# DAC.net
KiCad netlist of a schematic drawn in Altium Designer
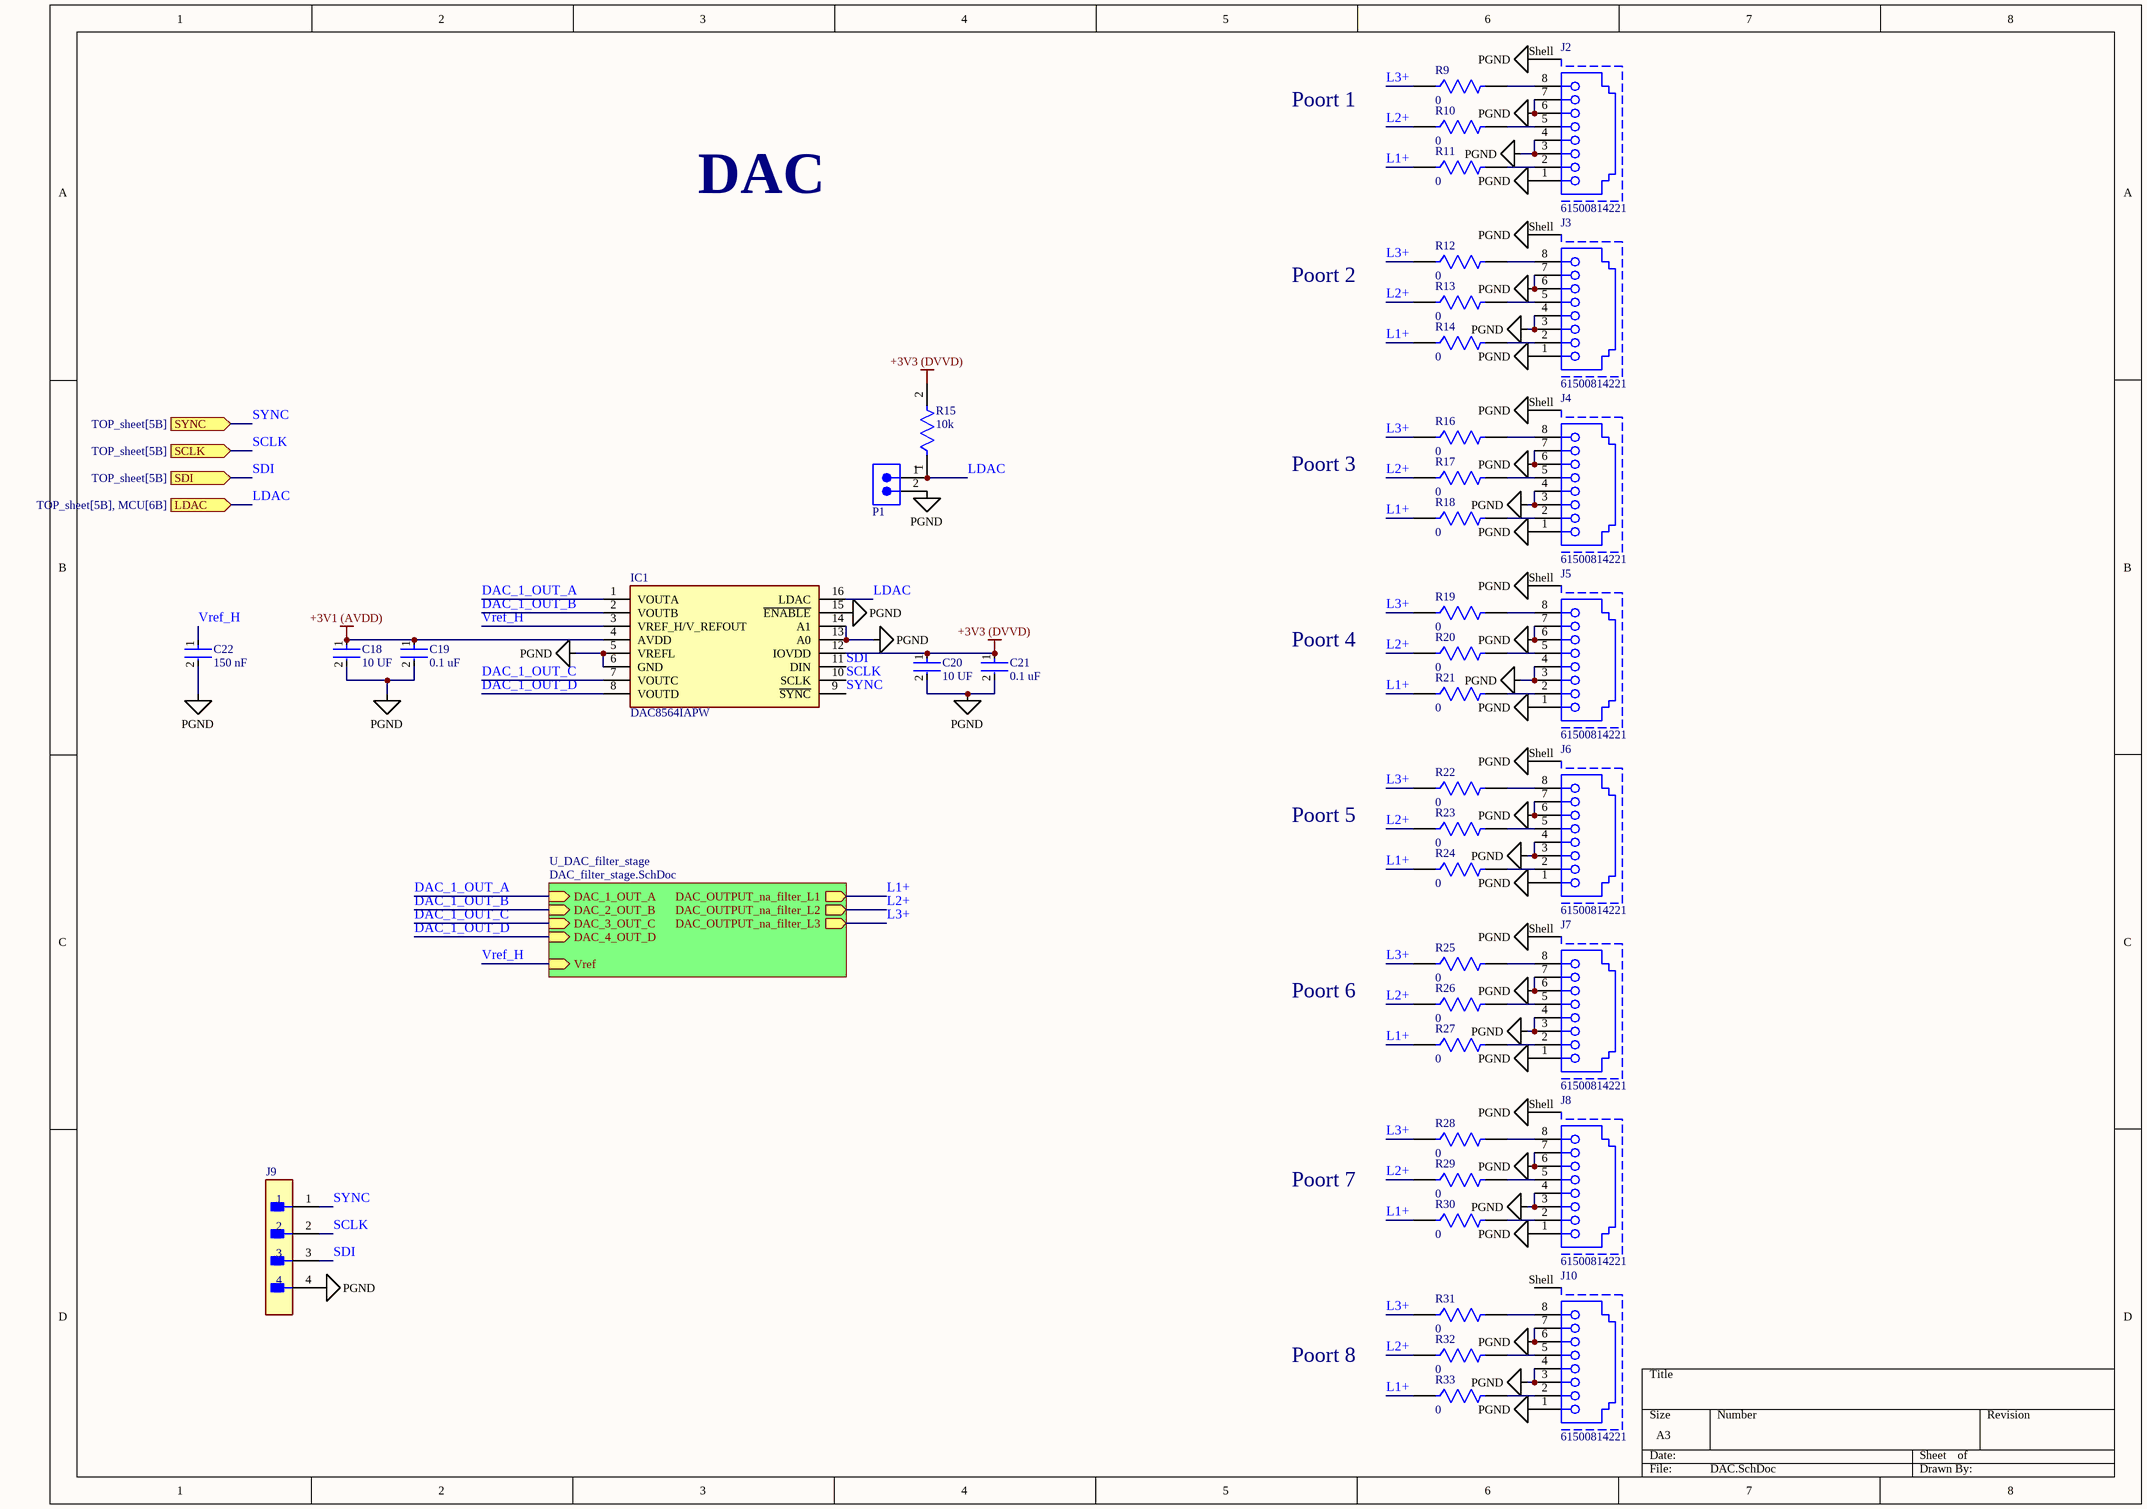
[diagram p0: DAC.SchDoc]

(export (version "E")
  (design (tool "Eeschema 10.0.6"))
  (components
    (comp (ref "C18")
      (value "10 UF")
      (footprint "FP-CC0603-DA-MFG")
      (description "CAP CER 10 UF 16V X7R 0603")
      (fields
        (field (name "OCTOPART") "https://octopart.com/cc0603krx7r7bb104-yageo-192941")
        (field (name "TOLERANCE") "0.1")
      )
      (libsource (lib "Altium Content Vault") (part "11868f565c42a9108669ba33697ecf6"))
    )
    (comp (ref "C19")
      (value "0.1 uF")
      (footprint "FP-CC0603-DA-MFG")
      (description "CAP CER 0.1UF 16V X7R 0603")
      (fields
        (field (name "OCTOPART") "https://octopart.com/cc0603krx7r7bb104-yageo-192941")
        (field (name "TOLERANCE") "0.1")
      )
      (libsource (lib "Altium Content Vault") (part "11868f565c42a9108669ba33697ecf6"))
    )
    (comp (ref "C20")
      (value "10 UF")
      (footprint "FP-CC0603-DA-MFG")
      (description "CAP CER 10 UF 16V X7R 0603")
      (fields
        (field (name "OCTOPART") "https://octopart.com/cc0603krx7r7bb104-yageo-192941")
        (field (name "TOLERANCE") "0.1")
      )
      (libsource (lib "Altium Content Vault") (part "11868f565c42a9108669ba33697ecf6"))
    )
    (comp (ref "C21")
      (value "0.1 uF")
      (footprint "FP-CC0603-DA-MFG")
      (description "CAP CER 0.1UF 16V X7R 0603")
      (fields
        (field (name "OCTOPART") "https://octopart.com/cc0603krx7r7bb104-yageo-192941")
        (field (name "TOLERANCE") "0.1")
      )
      (libsource (lib "Altium Content Vault") (part "11868f565c42a9108669ba33697ecf6"))
    )
    (comp (ref "C22")
      (value "150 nF")
      (footprint "FP-CC0603-DA-MFG")
      (description "CAP CER 0.1UF 16V X7R 0603")
      (fields
        (field (name "OCTOPART") "https://octopart.com/cc0603krx7r7bb104-yageo-192941")
        (field (name "TOLERANCE") "0.1")
      )
      (libsource (lib "Altium Content Vault") (part "11868f565c42a9108669ba33697ecf6"))
    )
    (comp (ref "IC1")
      (value "DAC8564IAPW")
      (footprint "SamacSys:SOP65P640X120-16N")
      (description "Integrated Circuit")
      (fields (field (name "MOUSER PART NUMBER") "595-DAC8564IAPW"))
      (libsource (lib "*") (part "DAC8564IAPW"))
    )
    (comp (ref "J2")
      (value "61500814221")
      (footprint "61500814221")
      (libsource (lib "Altium Content Vault") (part "8P8C - 1 Port - Shielded"))
    )
    (comp (ref "J3")
      (value "61500814221")
      (footprint "61500814221")
      (libsource (lib "Altium Content Vault") (part "8P8C - 1 Port - Shielded"))
    )
    (comp (ref "J4")
      (value "61500814221")
      (footprint "61500814221")
      (libsource (lib "Altium Content Vault") (part "8P8C - 1 Port - Shielded"))
    )
    (comp (ref "J5")
      (value "61500814221")
      (footprint "61500814221")
      (libsource (lib "Altium Content Vault") (part "8P8C - 1 Port - Shielded"))
    )
    (comp (ref "J6")
      (value "61500814221")
      (footprint "61500814221")
      (libsource (lib "Altium Content Vault") (part "8P8C - 1 Port - Shielded"))
    )
    (comp (ref "J7")
      (value "61500814221")
      (footprint "61500814221")
      (libsource (lib "Altium Content Vault") (part "8P8C - 1 Port - Shielded"))
    )
    (comp (ref "J8")
      (value "61500814221")
      (footprint "61500814221")
      (libsource (lib "Altium Content Vault") (part "8P8C - 1 Port - Shielded"))
    )
    (comp (ref "J9")
      (value "TSW-104-22-G-S")
      (footprint "FP-TSW-104-22-G-S-MFG")
      (description "GENERIC PART NUMBER: GPHA-1X04\r\nCONN HEADER VERT 4POS 2.54MM")
      (fields (field (name "GENERIC PART NUMBER") "GPHA-1X04"))
      (libsource (lib "Altium Content Vault") (part "299a8cea1bdcbc3624fe62c390fa72c"))
    )
    (comp (ref "J10")
      (value "61500814221")
      (footprint "61500814221")
      (libsource (lib "Altium Content Vault") (part "8P8C - 1 Port - Shielded"))
    )
    (comp (ref "P1")
      (value "TSW-102-26-T-S")
      (footprint "SMTC-TSW-102-26-XX-S")
      (description "0.025\" SQ Post Header, Through-hole, Vertical, -55 to 105 degC, 2.54 mm Pitch, 2-Pin, Male, RoHS")
      (fields (field (name "MANUFACTURER") "Samtec"))
      (libsource (lib "Altium Content Vault") (part "SMTC-TSW-102-X-X-S-X"))
    )
    (comp (ref "R9")
      (value "0")
      (footprint "FP-CRCW1206-MFG")
      (description "CRCW12060000ZSTA Zero Ohm Resistor, Jumper, 1206 [3216 Metric], Thick Film, 250 mW, Surface Mount")
      (libsource (lib "Altium Content Vault") (part "1029c3af85768c4190bb7ad29bc67b5"))
    )
    (comp (ref "R10")
      (value "0")
      (footprint "FP-CRCW1206-MFG")
      (description "CRCW12060000ZSTA Zero Ohm Resistor, Jumper, 1206 [3216 Metric], Thick Film, 250 mW, Surface Mount")
      (libsource (lib "Altium Content Vault") (part "1029c3af85768c4190bb7ad29bc67b5"))
    )
    (comp (ref "R11")
      (value "0")
      (footprint "FP-CRCW1206-MFG")
      (description "CRCW12060000ZSTA Zero Ohm Resistor, Jumper, 1206 [3216 Metric], Thick Film, 250 mW, Surface Mount")
      (libsource (lib "Altium Content Vault") (part "1029c3af85768c4190bb7ad29bc67b5"))
    )
    (comp (ref "R12")
      (value "0")
      (footprint "FP-CRCW1206-MFG")
      (description "CRCW12060000ZSTA Zero Ohm Resistor, Jumper, 1206 [3216 Metric], Thick Film, 250 mW, Surface Mount")
      (libsource (lib "Altium Content Vault") (part "1029c3af85768c4190bb7ad29bc67b5"))
    )
    (comp (ref "R13")
      (value "0")
      (footprint "FP-CRCW1206-MFG")
      (description "CRCW12060000ZSTA Zero Ohm Resistor, Jumper, 1206 [3216 Metric], Thick Film, 250 mW, Surface Mount")
      (libsource (lib "Altium Content Vault") (part "1029c3af85768c4190bb7ad29bc67b5"))
    )
    (comp (ref "R14")
      (value "0")
      (footprint "FP-CRCW1206-MFG")
      (description "CRCW12060000ZSTA Zero Ohm Resistor, Jumper, 1206 [3216 Metric], Thick Film, 250 mW, Surface Mount")
      (libsource (lib "Altium Content Vault") (part "1029c3af85768c4190bb7ad29bc67b5"))
    )
    (comp (ref "R15")
      (value "10k")
      (footprint "FP-RC1608-IPC_B")
      (description "Res Thick Film 0603 11kΩ 1% 0.1W ±100ppm/°C Molded SMD T/R")
      (fields (field (name "TOLERANCE") "1%"))
      (libsource (lib "") (part "1029c3af85768c4190bb7ad29bc67b5_1"))
    )
    (comp (ref "R16")
      (value "0")
      (footprint "FP-CRCW1206-MFG")
      (description "CRCW12060000ZSTA Zero Ohm Resistor, Jumper, 1206 [3216 Metric], Thick Film, 250 mW, Surface Mount")
      (libsource (lib "Altium Content Vault") (part "1029c3af85768c4190bb7ad29bc67b5"))
    )
    (comp (ref "R17")
      (value "0")
      (footprint "FP-CRCW1206-MFG")
      (description "CRCW12060000ZSTA Zero Ohm Resistor, Jumper, 1206 [3216 Metric], Thick Film, 250 mW, Surface Mount")
      (libsource (lib "Altium Content Vault") (part "1029c3af85768c4190bb7ad29bc67b5"))
    )
    (comp (ref "R18")
      (value "0")
      (footprint "FP-CRCW1206-MFG")
      (description "CRCW12060000ZSTA Zero Ohm Resistor, Jumper, 1206 [3216 Metric], Thick Film, 250 mW, Surface Mount")
      (libsource (lib "Altium Content Vault") (part "1029c3af85768c4190bb7ad29bc67b5"))
    )
    (comp (ref "R19")
      (value "0")
      (footprint "FP-CRCW1206-MFG")
      (description "CRCW12060000ZSTA Zero Ohm Resistor, Jumper, 1206 [3216 Metric], Thick Film, 250 mW, Surface Mount")
      (libsource (lib "Altium Content Vault") (part "1029c3af85768c4190bb7ad29bc67b5"))
    )
    (comp (ref "R20")
      (value "0")
      (footprint "FP-CRCW1206-MFG")
      (description "CRCW12060000ZSTA Zero Ohm Resistor, Jumper, 1206 [3216 Metric], Thick Film, 250 mW, Surface Mount")
      (libsource (lib "Altium Content Vault") (part "1029c3af85768c4190bb7ad29bc67b5"))
    )
    (comp (ref "R21")
      (value "0")
      (footprint "FP-CRCW1206-MFG")
      (description "CRCW12060000ZSTA Zero Ohm Resistor, Jumper, 1206 [3216 Metric], Thick Film, 250 mW, Surface Mount")
      (libsource (lib "Altium Content Vault") (part "1029c3af85768c4190bb7ad29bc67b5"))
    )
    (comp (ref "R22")
      (value "0")
      (footprint "FP-CRCW1206-MFG")
      (description "CRCW12060000ZSTA Zero Ohm Resistor, Jumper, 1206 [3216 Metric], Thick Film, 250 mW, Surface Mount")
      (libsource (lib "Altium Content Vault") (part "1029c3af85768c4190bb7ad29bc67b5"))
    )
    (comp (ref "R23")
      (value "0")
      (footprint "FP-CRCW1206-MFG")
      (description "CRCW12060000ZSTA Zero Ohm Resistor, Jumper, 1206 [3216 Metric], Thick Film, 250 mW, Surface Mount")
      (libsource (lib "Altium Content Vault") (part "1029c3af85768c4190bb7ad29bc67b5"))
    )
    (comp (ref "R24")
      (value "0")
      (footprint "FP-CRCW1206-MFG")
      (description "CRCW12060000ZSTA Zero Ohm Resistor, Jumper, 1206 [3216 Metric], Thick Film, 250 mW, Surface Mount")
      (libsource (lib "Altium Content Vault") (part "1029c3af85768c4190bb7ad29bc67b5"))
    )
    (comp (ref "R25")
      (value "0")
      (footprint "FP-CRCW1206-MFG")
      (description "CRCW12060000ZSTA Zero Ohm Resistor, Jumper, 1206 [3216 Metric], Thick Film, 250 mW, Surface Mount")
      (libsource (lib "Altium Content Vault") (part "1029c3af85768c4190bb7ad29bc67b5"))
    )
    (comp (ref "R26")
      (value "0")
      (footprint "FP-CRCW1206-MFG")
      (description "CRCW12060000ZSTA Zero Ohm Resistor, Jumper, 1206 [3216 Metric], Thick Film, 250 mW, Surface Mount")
      (libsource (lib "Altium Content Vault") (part "1029c3af85768c4190bb7ad29bc67b5"))
    )
    (comp (ref "R27")
      (value "0")
      (footprint "FP-CRCW1206-MFG")
      (description "CRCW12060000ZSTA Zero Ohm Resistor, Jumper, 1206 [3216 Metric], Thick Film, 250 mW, Surface Mount")
      (libsource (lib "Altium Content Vault") (part "1029c3af85768c4190bb7ad29bc67b5"))
    )
    (comp (ref "R28")
      (value "0")
      (footprint "FP-CRCW1206-MFG")
      (description "CRCW12060000ZSTA Zero Ohm Resistor, Jumper, 1206 [3216 Metric], Thick Film, 250 mW, Surface Mount")
      (libsource (lib "Altium Content Vault") (part "1029c3af85768c4190bb7ad29bc67b5"))
    )
    (comp (ref "R29")
      (value "0")
      (footprint "FP-CRCW1206-MFG")
      (description "CRCW12060000ZSTA Zero Ohm Resistor, Jumper, 1206 [3216 Metric], Thick Film, 250 mW, Surface Mount")
      (libsource (lib "Altium Content Vault") (part "1029c3af85768c4190bb7ad29bc67b5"))
    )
    (comp (ref "R30")
      (value "0")
      (footprint "FP-CRCW1206-MFG")
      (description "CRCW12060000ZSTA Zero Ohm Resistor, Jumper, 1206 [3216 Metric], Thick Film, 250 mW, Surface Mount")
      (libsource (lib "Altium Content Vault") (part "1029c3af85768c4190bb7ad29bc67b5"))
    )
    (comp (ref "R31")
      (value "0")
      (footprint "FP-CRCW1206-MFG")
      (description "CRCW12060000ZSTA Zero Ohm Resistor, Jumper, 1206 [3216 Metric], Thick Film, 250 mW, Surface Mount")
      (libsource (lib "Altium Content Vault") (part "1029c3af85768c4190bb7ad29bc67b5"))
    )
    (comp (ref "R32")
      (value "0")
      (footprint "FP-CRCW1206-MFG")
      (description "CRCW12060000ZSTA Zero Ohm Resistor, Jumper, 1206 [3216 Metric], Thick Film, 250 mW, Surface Mount")
      (libsource (lib "Altium Content Vault") (part "1029c3af85768c4190bb7ad29bc67b5"))
    )
    (comp (ref "R33")
      (value "0")
      (footprint "FP-CRCW1206-MFG")
      (description "CRCW12060000ZSTA Zero Ohm Resistor, Jumper, 1206 [3216 Metric], Thick Film, 250 mW, Surface Mount")
      (libsource (lib "Altium Content Vault") (part "1029c3af85768c4190bb7ad29bc67b5"))
    )
  )
  (nets
    (net (code "1") (name "+3V1 (AVDD)") (class "Default")
      (node (ref "C18") (pin "1") (pinfunction "1_1") (pintype "passive"))
      (node (ref "C19") (pin "1") (pinfunction "1_1") (pintype "passive"))
      (node (ref "IC1") (pin "4") (pinfunction "AVDD_4") (pintype "passive"))
    )
    (net (code "2") (name "+3V3 (DVVD)") (class "Default")
      (node (ref "C20") (pin "1") (pinfunction "1_1") (pintype "passive"))
      (node (ref "C21") (pin "1") (pinfunction "1_1") (pintype "passive"))
      (node (ref "IC1") (pin "12") (pinfunction "IOVDD_12") (pintype "passive"))
      (node (ref "R15") (pin "2") (pinfunction "2_2") (pintype "passive"))
    )
    (net (code "3") (name "/DAC_1_OUT_A") (class "Default")
      (node (ref "IC1") (pin "1") (pinfunction "VOUTA_1") (pintype "passive"))
    )
    (net (code "4") (name "/DAC_1_OUT_B") (class "Default")
      (node (ref "IC1") (pin "2") (pinfunction "VOUTB_2") (pintype "passive"))
    )
    (net (code "5") (name "/DAC_1_OUT_C") (class "Default")
      (node (ref "IC1") (pin "7") (pinfunction "VOUTC_7") (pintype "passive"))
    )
    (net (code "6") (name "/DAC_1_OUT_D") (class "Default")
      (node (ref "IC1") (pin "8") (pinfunction "VOUTD_8") (pintype "passive"))
    )
    (net (code "7") (name "/L1+") (class "Default")
      (node (ref "R11") (pin "1") (pinfunction "1_1") (pintype "passive"))
      (node (ref "R14") (pin "1") (pinfunction "1_1") (pintype "passive"))
      (node (ref "R18") (pin "1") (pinfunction "1_1") (pintype "passive"))
      (node (ref "R21") (pin "1") (pinfunction "1_1") (pintype "passive"))
      (node (ref "R24") (pin "1") (pinfunction "1_1") (pintype "passive"))
      (node (ref "R27") (pin "1") (pinfunction "1_1") (pintype "passive"))
      (node (ref "R30") (pin "1") (pinfunction "1_1") (pintype "passive"))
      (node (ref "R33") (pin "1") (pinfunction "1_1") (pintype "passive"))
    )
    (net (code "8") (name "/L2+") (class "Default")
      (node (ref "R10") (pin "1") (pinfunction "1_1") (pintype "passive"))
      (node (ref "R13") (pin "1") (pinfunction "1_1") (pintype "passive"))
      (node (ref "R17") (pin "1") (pinfunction "1_1") (pintype "passive"))
      (node (ref "R20") (pin "1") (pinfunction "1_1") (pintype "passive"))
      (node (ref "R23") (pin "1") (pinfunction "1_1") (pintype "passive"))
      (node (ref "R26") (pin "1") (pinfunction "1_1") (pintype "passive"))
      (node (ref "R29") (pin "1") (pinfunction "1_1") (pintype "passive"))
      (node (ref "R32") (pin "1") (pinfunction "1_1") (pintype "passive"))
    )
    (net (code "9") (name "/L3+") (class "Default")
      (node (ref "R12") (pin "1") (pinfunction "1_1") (pintype "passive"))
      (node (ref "R16") (pin "1") (pinfunction "1_1") (pintype "passive"))
      (node (ref "R19") (pin "1") (pinfunction "1_1") (pintype "passive"))
      (node (ref "R22") (pin "1") (pinfunction "1_1") (pintype "passive"))
      (node (ref "R25") (pin "1") (pinfunction "1_1") (pintype "passive"))
      (node (ref "R28") (pin "1") (pinfunction "1_1") (pintype "passive"))
      (node (ref "R31") (pin "1") (pinfunction "1_1") (pintype "passive"))
      (node (ref "R9") (pin "1") (pinfunction "1_1") (pintype "passive"))
    )
    (net (code "10") (name "/LDAC") (class "Default")
      (node (ref "IC1") (pin "16") (pinfunction "LDAC_16") (pintype "passive"))
      (node (ref "P1") (pin "1") (pinfunction "1_1") (pintype "passive"))
      (node (ref "R15") (pin "1") (pinfunction "1_1") (pintype "passive"))
    )
    (net (code "11") (name "/SCLK") (class "Default")
      (node (ref "IC1") (pin "10") (pinfunction "SCLK_10") (pintype "passive"))
      (node (ref "J9") (pin "2") (pinfunction "2_2") (pintype "passive"))
    )
    (net (code "12") (name "/SDI") (class "Default")
      (node (ref "IC1") (pin "11") (pinfunction "DIN_11") (pintype "passive"))
      (node (ref "J9") (pin "3") (pinfunction "3_3") (pintype "passive"))
    )
    (net (code "13") (name "/SYNC") (class "Default")
      (node (ref "IC1") (pin "9") (pinfunction "~{SYNC}_9") (pintype "passive"))
      (node (ref "J9") (pin "1") (pinfunction "1_1") (pintype "passive"))
    )
    (net (code "14") (name "/Vref_H") (class "Default")
      (node (ref "C22") (pin "1") (pinfunction "1_1") (pintype "passive"))
      (node (ref "IC1") (pin "3") (pinfunction "VREF_H/V_REFOUT_3") (pintype "passive"))
    )
    (net (code "15") (name "Net-(J2-Pad2)") (class "Default")
      (node (ref "J2") (pin "2") (pinfunction "2_2") (pintype "passive"))
      (node (ref "R11") (pin "2") (pinfunction "2_2") (pintype "passive"))
    )
    (net (code "16") (name "Net-(J2-Pad5)") (class "Default")
      (node (ref "J2") (pin "5") (pinfunction "5_5") (pintype "passive"))
      (node (ref "R10") (pin "2") (pinfunction "2_2") (pintype "passive"))
    )
    (net (code "17") (name "Net-(J2-Pad8)") (class "Default")
      (node (ref "J2") (pin "8") (pinfunction "8_8") (pintype "passive"))
      (node (ref "R9") (pin "2") (pinfunction "2_2") (pintype "passive"))
    )
    (net (code "18") (name "Net-(J3-Pad2)") (class "Default")
      (node (ref "J3") (pin "2") (pinfunction "2_2") (pintype "passive"))
      (node (ref "R14") (pin "2") (pinfunction "2_2") (pintype "passive"))
    )
    (net (code "19") (name "Net-(J3-Pad5)") (class "Default")
      (node (ref "J3") (pin "5") (pinfunction "5_5") (pintype "passive"))
      (node (ref "R13") (pin "2") (pinfunction "2_2") (pintype "passive"))
    )
    (net (code "20") (name "Net-(J3-Pad8)") (class "Default")
      (node (ref "J3") (pin "8") (pinfunction "8_8") (pintype "passive"))
      (node (ref "R12") (pin "2") (pinfunction "2_2") (pintype "passive"))
    )
    (net (code "21") (name "Net-(J4-Pad2)") (class "Default")
      (node (ref "J4") (pin "2") (pinfunction "2_2") (pintype "passive"))
      (node (ref "R18") (pin "2") (pinfunction "2_2") (pintype "passive"))
    )
    (net (code "22") (name "Net-(J4-Pad5)") (class "Default")
      (node (ref "J4") (pin "5") (pinfunction "5_5") (pintype "passive"))
      (node (ref "R17") (pin "2") (pinfunction "2_2") (pintype "passive"))
    )
    (net (code "23") (name "Net-(J4-Pad8)") (class "Default")
      (node (ref "J4") (pin "8") (pinfunction "8_8") (pintype "passive"))
      (node (ref "R16") (pin "2") (pinfunction "2_2") (pintype "passive"))
    )
    (net (code "24") (name "Net-(J5-Pad2)") (class "Default")
      (node (ref "J5") (pin "2") (pinfunction "2_2") (pintype "passive"))
      (node (ref "R21") (pin "2") (pinfunction "2_2") (pintype "passive"))
    )
    (net (code "25") (name "Net-(J5-Pad5)") (class "Default")
      (node (ref "J5") (pin "5") (pinfunction "5_5") (pintype "passive"))
      (node (ref "R20") (pin "2") (pinfunction "2_2") (pintype "passive"))
    )
    (net (code "26") (name "Net-(J5-Pad8)") (class "Default")
      (node (ref "J5") (pin "8") (pinfunction "8_8") (pintype "passive"))
      (node (ref "R19") (pin "2") (pinfunction "2_2") (pintype "passive"))
    )
    (net (code "27") (name "Net-(J6-Pad2)") (class "Default")
      (node (ref "J6") (pin "2") (pinfunction "2_2") (pintype "passive"))
      (node (ref "R24") (pin "2") (pinfunction "2_2") (pintype "passive"))
    )
    (net (code "28") (name "Net-(J6-Pad5)") (class "Default")
      (node (ref "J6") (pin "5") (pinfunction "5_5") (pintype "passive"))
      (node (ref "R23") (pin "2") (pinfunction "2_2") (pintype "passive"))
    )
    (net (code "29") (name "Net-(J6-Pad8)") (class "Default")
      (node (ref "J6") (pin "8") (pinfunction "8_8") (pintype "passive"))
      (node (ref "R22") (pin "2") (pinfunction "2_2") (pintype "passive"))
    )
    (net (code "30") (name "Net-(J7-Pad2)") (class "Default")
      (node (ref "J7") (pin "2") (pinfunction "2_2") (pintype "passive"))
      (node (ref "R27") (pin "2") (pinfunction "2_2") (pintype "passive"))
    )
    (net (code "31") (name "Net-(J7-Pad5)") (class "Default")
      (node (ref "J7") (pin "5") (pinfunction "5_5") (pintype "passive"))
      (node (ref "R26") (pin "2") (pinfunction "2_2") (pintype "passive"))
    )
    (net (code "32") (name "Net-(J7-Pad8)") (class "Default")
      (node (ref "J7") (pin "8") (pinfunction "8_8") (pintype "passive"))
      (node (ref "R25") (pin "2") (pinfunction "2_2") (pintype "passive"))
    )
    (net (code "33") (name "Net-(J8-Pad2)") (class "Default")
      (node (ref "J8") (pin "2") (pinfunction "2_2") (pintype "passive"))
      (node (ref "R30") (pin "2") (pinfunction "2_2") (pintype "passive"))
    )
    (net (code "34") (name "Net-(J8-Pad5)") (class "Default")
      (node (ref "J8") (pin "5") (pinfunction "5_5") (pintype "passive"))
      (node (ref "R29") (pin "2") (pinfunction "2_2") (pintype "passive"))
    )
    (net (code "35") (name "Net-(J8-Pad8)") (class "Default")
      (node (ref "J8") (pin "8") (pinfunction "8_8") (pintype "passive"))
      (node (ref "R28") (pin "2") (pinfunction "2_2") (pintype "passive"))
    )
    (net (code "36") (name "Net-(J10-Pad2)") (class "Default")
      (node (ref "J10") (pin "2") (pinfunction "2_2") (pintype "passive"))
      (node (ref "R33") (pin "2") (pinfunction "2_2") (pintype "passive"))
    )
    (net (code "37") (name "Net-(J10-Pad5)") (class "Default")
      (node (ref "J10") (pin "5") (pinfunction "5_5") (pintype "passive"))
      (node (ref "R32") (pin "2") (pinfunction "2_2") (pintype "passive"))
    )
    (net (code "38") (name "Net-(J10-Pad8)") (class "Default")
      (node (ref "J10") (pin "8") (pinfunction "8_8") (pintype "passive"))
      (node (ref "R31") (pin "2") (pinfunction "2_2") (pintype "passive"))
    )
    (net (code "39") (name "PGND") (class "Default")
      (node (ref "C18") (pin "2") (pinfunction "2_2") (pintype "passive"))
      (node (ref "C19") (pin "2") (pinfunction "2_2") (pintype "passive"))
      (node (ref "C20") (pin "2") (pinfunction "2_2") (pintype "passive"))
      (node (ref "C21") (pin "2") (pinfunction "2_2") (pintype "passive"))
      (node (ref "C22") (pin "2") (pinfunction "2_2") (pintype "passive"))
      (node (ref "IC1") (pin "13") (pinfunction "A0_13") (pintype "passive"))
      (node (ref "IC1") (pin "14") (pinfunction "A1_14") (pintype "passive"))
      (node (ref "IC1") (pin "15") (pinfunction "~{ENABLE}_15") (pintype "passive"))
      (node (ref "IC1") (pin "5") (pinfunction "VREFL_5") (pintype "passive"))
      (node (ref "IC1") (pin "6") (pinfunction "GND_6") (pintype "passive"))
      (node (ref "J10") (pin "1") (pinfunction "1_1") (pintype "passive"))
      (node (ref "J10") (pin "3") (pinfunction "3_3") (pintype "passive"))
      (node (ref "J10") (pin "4") (pinfunction "4_4") (pintype "passive"))
      (node (ref "J10") (pin "6") (pinfunction "6_6") (pintype "passive"))
      (node (ref "J10") (pin "7") (pinfunction "7_7") (pintype "passive"))
      (node (ref "J2") (pin "1") (pinfunction "1_1") (pintype "passive"))
      (node (ref "J2") (pin "3") (pinfunction "3_3") (pintype "passive"))
      (node (ref "J2") (pin "4") (pinfunction "4_4") (pintype "passive"))
      (node (ref "J2") (pin "6") (pinfunction "6_6") (pintype "passive"))
      (node (ref "J2") (pin "7") (pinfunction "7_7") (pintype "passive"))
      (node (ref "J2") (pin "Shell") (pinfunction "Shell_Shell") (pintype "passive"))
      (node (ref "J3") (pin "1") (pinfunction "1_1") (pintype "passive"))
      (node (ref "J3") (pin "3") (pinfunction "3_3") (pintype "passive"))
      (node (ref "J3") (pin "4") (pinfunction "4_4") (pintype "passive"))
      (node (ref "J3") (pin "6") (pinfunction "6_6") (pintype "passive"))
      (node (ref "J3") (pin "7") (pinfunction "7_7") (pintype "passive"))
      (node (ref "J3") (pin "Shell") (pinfunction "Shell_Shell") (pintype "passive"))
      (node (ref "J4") (pin "1") (pinfunction "1_1") (pintype "passive"))
      (node (ref "J4") (pin "3") (pinfunction "3_3") (pintype "passive"))
      (node (ref "J4") (pin "4") (pinfunction "4_4") (pintype "passive"))
      (node (ref "J4") (pin "6") (pinfunction "6_6") (pintype "passive"))
      (node (ref "J4") (pin "7") (pinfunction "7_7") (pintype "passive"))
      (node (ref "J4") (pin "Shell") (pinfunction "Shell_Shell") (pintype "passive"))
      (node (ref "J5") (pin "1") (pinfunction "1_1") (pintype "passive"))
      (node (ref "J5") (pin "3") (pinfunction "3_3") (pintype "passive"))
      (node (ref "J5") (pin "4") (pinfunction "4_4") (pintype "passive"))
      (node (ref "J5") (pin "6") (pinfunction "6_6") (pintype "passive"))
      (node (ref "J5") (pin "7") (pinfunction "7_7") (pintype "passive"))
      (node (ref "J5") (pin "Shell") (pinfunction "Shell_Shell") (pintype "passive"))
      (node (ref "J6") (pin "1") (pinfunction "1_1") (pintype "passive"))
      (node (ref "J6") (pin "3") (pinfunction "3_3") (pintype "passive"))
      (node (ref "J6") (pin "4") (pinfunction "4_4") (pintype "passive"))
      (node (ref "J6") (pin "6") (pinfunction "6_6") (pintype "passive"))
      (node (ref "J6") (pin "7") (pinfunction "7_7") (pintype "passive"))
      (node (ref "J6") (pin "Shell") (pinfunction "Shell_Shell") (pintype "passive"))
      (node (ref "J7") (pin "1") (pinfunction "1_1") (pintype "passive"))
      (node (ref "J7") (pin "3") (pinfunction "3_3") (pintype "passive"))
      (node (ref "J7") (pin "4") (pinfunction "4_4") (pintype "passive"))
      (node (ref "J7") (pin "6") (pinfunction "6_6") (pintype "passive"))
      (node (ref "J7") (pin "7") (pinfunction "7_7") (pintype "passive"))
      (node (ref "J7") (pin "Shell") (pinfunction "Shell_Shell") (pintype "passive"))
      (node (ref "J8") (pin "1") (pinfunction "1_1") (pintype "passive"))
      (node (ref "J8") (pin "3") (pinfunction "3_3") (pintype "passive"))
      (node (ref "J8") (pin "4") (pinfunction "4_4") (pintype "passive"))
      (node (ref "J8") (pin "6") (pinfunction "6_6") (pintype "passive"))
      (node (ref "J8") (pin "7") (pinfunction "7_7") (pintype "passive"))
      (node (ref "J8") (pin "Shell") (pinfunction "Shell_Shell") (pintype "passive"))
      (node (ref "J9") (pin "4") (pinfunction "4_4") (pintype "passive"))
      (node (ref "P1") (pin "2") (pinfunction "2_2") (pintype "passive"))
    )
    (net (code "40") (name "unconnected-(J10-PadShell)") (class "Default")
      (node (ref "J10") (pin "Shell") (pinfunction "Shell_Shell") (pintype "passive"))
    )
  )
)
